# main_IO.net
KiCad netlist of a schematic drawn in Altium Designer
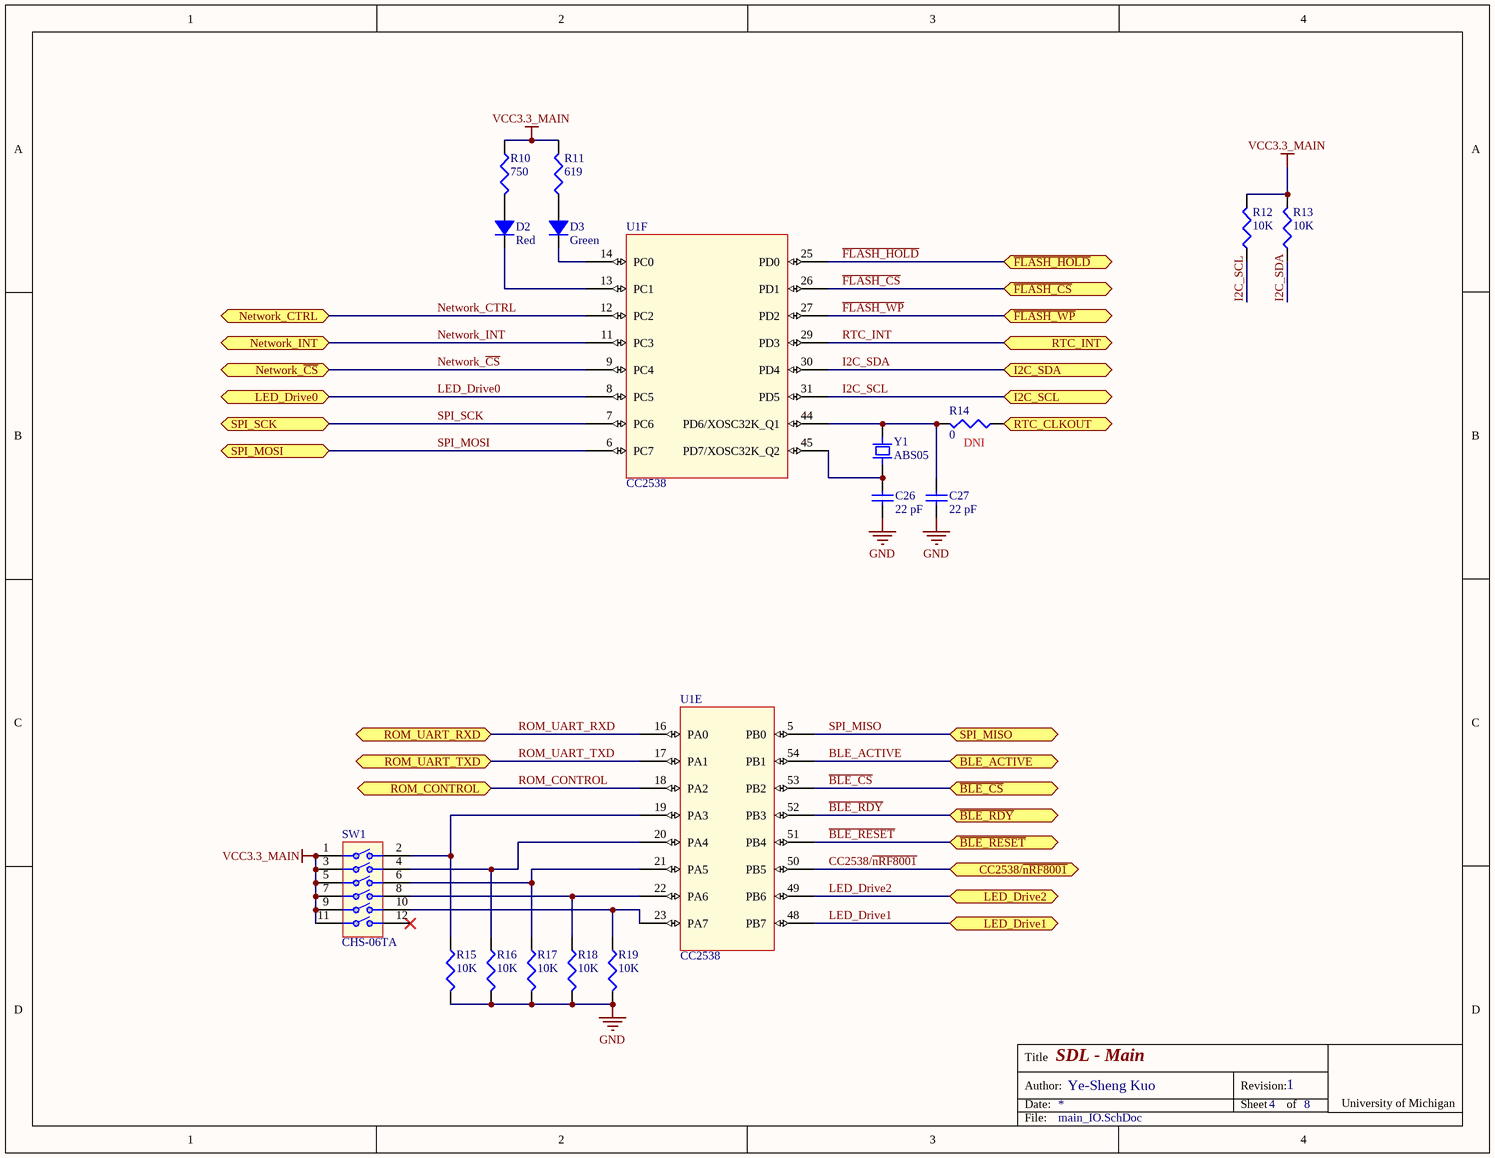
[diagram p0: main_IO.SchDoc]

(export (version "E")
  (design (tool "Eeschema 10.0.6"))
  (components
    (comp (ref "C26")
      (value "22 pF")
      (footprint "0402")
      (description "Ceramic capacitor, 22 pF, 0402 package")
      (fields (field (name "TOLERANCE") "2%") (field (name "Comment") "Ceramic capacitor"))
      (libsource (lib "rlc") (part "C_22p_0402_ceramic"))
    )
    (comp (ref "C27")
      (value "22 pF")
      (footprint "0402")
      (description "Ceramic capacitor, 22 pF, 0402 package")
      (fields (field (name "TOLERANCE") "2%") (field (name "Comment") "Ceramic capacitor"))
      (libsource (lib "rlc") (part "C_22p_0402_ceramic"))
    )
    (comp (ref "D2")
      (value "LED, Red")
      (footprint "0402 - DIODE")
      (description "LED, Red, 0402")
      (fields (field (name "COLOR") "Red"))
      (libsource (lib "rlc") (part "D_LED_RED_0402"))
    )
    (comp (ref "D3")
      (value "LED, Green")
      (footprint "0402 - DIODE")
      (description "LED, Green,  0402")
      (fields (field (name "COLOR") "Green"))
      (libsource (lib "rlc") (part "D_LED_GREEN_0402"))
    )
    (comp (ref "R10")
      (value "750")
      (footprint "0402")
      (description "Chip resistor, 750, 0402 package")
      (fields (field (name "TOLERANCE") "1%") (field (name "POWER") "1/16 W"))
      (libsource (lib "rlc") (part "R_750_0402"))
    )
    (comp (ref "R11")
      (value "619")
      (footprint "0402")
      (description "Chip resistor, 619, 0402 package")
      (fields (field (name "TOLERANCE") "1%") (field (name "POWER") "1/16 W"))
      (libsource (lib "rlc") (part "R_619_0402"))
    )
    (comp (ref "R12")
      (value "10K")
      (footprint "0402")
      (description "Chip resistor, 10K, 0402 package")
      (fields (field (name "TOLERANCE") "1%") (field (name "POWER") "1/16 W"))
      (libsource (lib "rlc") (part "R_10K_0402"))
    )
    (comp (ref "R13")
      (value "10K")
      (footprint "0402")
      (description "Chip resistor, 10K, 0402 package")
      (fields (field (name "TOLERANCE") "1%") (field (name "POWER") "1/16 W"))
      (libsource (lib "rlc") (part "R_10K_0402"))
    )
    (comp (ref "R14")
      (value "0")
      (footprint "0402")
      (description "Chip resistor, 0, 0402 package")
      (fields (field (name "Comment") "Chip resistor"))
      (libsource (lib "rlc") (part "R_0_0402"))
    )
    (comp (ref "R15")
      (value "10K")
      (footprint "0402")
      (description "Chip resistor, 10K, 0402 package")
      (fields (field (name "TOLERANCE") "1%") (field (name "POWER") "1/16 W"))
      (libsource (lib "rlc") (part "R_10K_0402"))
    )
    (comp (ref "R16")
      (value "10K")
      (footprint "0402")
      (description "Chip resistor, 10K, 0402 package")
      (fields (field (name "TOLERANCE") "1%") (field (name "POWER") "1/16 W"))
      (libsource (lib "rlc") (part "R_10K_0402"))
    )
    (comp (ref "R17")
      (value "10K")
      (footprint "0402")
      (description "Chip resistor, 10K, 0402 package")
      (fields (field (name "TOLERANCE") "1%") (field (name "POWER") "1/16 W"))
      (libsource (lib "rlc") (part "R_10K_0402"))
    )
    (comp (ref "R18")
      (value "10K")
      (footprint "0402")
      (description "Chip resistor, 10K, 0402 package")
      (fields (field (name "TOLERANCE") "1%") (field (name "POWER") "1/16 W"))
      (libsource (lib "rlc") (part "R_10K_0402"))
    )
    (comp (ref "R19")
      (value "10K")
      (footprint "0402")
      (description "Chip resistor, 10K, 0402 package")
      (fields (field (name "TOLERANCE") "1%") (field (name "POWER") "1/16 W"))
      (libsource (lib "rlc") (part "R_10K_0402"))
    )
    (comp (ref "SW1")
      (value "CHS-06TA")
      (footprint "CHS-06TA")
      (description "SLIDE SWITCHES")
      (libsource (lib "sdl") (part "CHS-06TA"))
    )
    (comp (ref "U1")
      (value "CC2538")
      (footprint "QFN56")
      (description "A Powerful System-On-Chip for 2.4-GHz IEEE 802.15.4, 6LoWPAN  and ZigBee Applications")
      (libsource (lib "sdl") (part "CC2538"))
    )
    (comp (ref "Y1")
      (value "ABS05")
      (footprint "ABS05")
      (description "32768 Hz SMD Low profile crystal")
      (libsource (lib "crystal_oscillators_rtc") (part "ABS05"))
    )
  )
  (nets
    (net (code "1") (name "/BLE_ACTIVE") (class "Default")
      (node (ref "U1") (pin "54") (pinfunction "PB1_54") (pintype "bidirectional"))
    )
    (net (code "2") (name "/CC2538{slash}~{nRF8001}") (class "Default")
      (node (ref "U1") (pin "50") (pinfunction "PB5_50") (pintype "bidirectional"))
    )
    (net (code "3") (name "/I2C_SCL") (class "Default")
      (node (ref "R12") (pin "2") (pintype "passive"))
      (node (ref "U1") (pin "31") (pinfunction "PD5_31") (pintype "bidirectional"))
    )
    (net (code "4") (name "/I2C_SDA") (class "Default")
      (node (ref "R13") (pin "2") (pintype "passive"))
      (node (ref "U1") (pin "30") (pinfunction "PD4_30") (pintype "bidirectional"))
    )
    (net (code "5") (name "/LED_Drive0") (class "Default")
      (node (ref "U1") (pin "8") (pinfunction "PC5_8") (pintype "bidirectional"))
    )
    (net (code "6") (name "/LED_Drive1") (class "Default")
      (node (ref "U1") (pin "48") (pinfunction "PB7_48") (pintype "bidirectional"))
    )
    (net (code "7") (name "/LED_Drive2") (class "Default")
      (node (ref "U1") (pin "49") (pinfunction "PB6_49") (pintype "bidirectional"))
    )
    (net (code "8") (name "/Network_CTRL") (class "Default")
      (node (ref "U1") (pin "12") (pinfunction "PC2_12") (pintype "bidirectional"))
    )
    (net (code "9") (name "/Network_INT") (class "Default")
      (node (ref "U1") (pin "11") (pinfunction "PC3_11") (pintype "bidirectional"))
    )
    (net (code "10") (name "/Network_~{CS}") (class "Default")
      (node (ref "U1") (pin "9") (pinfunction "PC4_9") (pintype "bidirectional"))
    )
    (net (code "11") (name "/ROM_CONTROL") (class "Default")
      (node (ref "U1") (pin "18") (pinfunction "PA2_18") (pintype "bidirectional"))
    )
    (net (code "12") (name "/ROM_UART_RXD") (class "Default")
      (node (ref "U1") (pin "16") (pinfunction "PA0_16") (pintype "bidirectional"))
    )
    (net (code "13") (name "/ROM_UART_TXD") (class "Default")
      (node (ref "U1") (pin "17") (pinfunction "PA1_17") (pintype "bidirectional"))
    )
    (net (code "14") (name "/RTC_CLKOUT") (class "Default") (node (ref "R14") (pin "2") (pintype "passive")))
    (net (code "15") (name "/RTC_INT") (class "Default")
      (node (ref "U1") (pin "29") (pinfunction "PD3_29") (pintype "bidirectional"))
    )
    (net (code "16") (name "/SPI_MISO") (class "Default")
      (node (ref "U1") (pin "5") (pinfunction "PB0_5") (pintype "bidirectional"))
    )
    (net (code "17") (name "/SPI_MOSI") (class "Default")
      (node (ref "U1") (pin "6") (pinfunction "PC7_6") (pintype "bidirectional"))
    )
    (net (code "18") (name "/SPI_SCK") (class "Default")
      (node (ref "U1") (pin "7") (pinfunction "PC6_7") (pintype "bidirectional"))
    )
    (net (code "19") (name "/~{BLE_CS}") (class "Default")
      (node (ref "U1") (pin "53") (pinfunction "PB2_53") (pintype "bidirectional"))
    )
    (net (code "20") (name "/~{BLE_RDY}") (class "Default")
      (node (ref "U1") (pin "52") (pinfunction "PB3_52") (pintype "bidirectional"))
    )
    (net (code "21") (name "/~{BLE_RESET}") (class "Default")
      (node (ref "U1") (pin "51") (pinfunction "PB4_51") (pintype "bidirectional"))
    )
    (net (code "22") (name "/~{FLASH_CS}") (class "Default")
      (node (ref "U1") (pin "26") (pinfunction "PD1_26") (pintype "bidirectional"))
    )
    (net (code "23") (name "/~{FLASH_HOLD}") (class "Default")
      (node (ref "U1") (pin "25") (pinfunction "PD0_25") (pintype "bidirectional"))
    )
    (net (code "24") (name "/~{FLASH_WP}") (class "Default")
      (node (ref "U1") (pin "27") (pinfunction "PD2_27") (pintype "bidirectional"))
    )
    (net (code "25") (name "GND") (class "Default")
      (node (ref "C26") (pin "2") (pintype "passive"))
      (node (ref "C27") (pin "2") (pintype "passive"))
      (node (ref "R15") (pin "1") (pintype "passive"))
      (node (ref "R16") (pin "1") (pintype "passive"))
      (node (ref "R17") (pin "1") (pintype "passive"))
      (node (ref "R18") (pin "1") (pintype "passive"))
      (node (ref "R19") (pin "1") (pintype "passive"))
    )
    (net (code "26") (name "Net-(D2-Pad1)") (class "Default")
      (node (ref "D2") (pin "1") (pintype "passive"))
      (node (ref "R10") (pin "1") (pintype "passive"))
    )
    (net (code "27") (name "Net-(D3-Pad1)") (class "Default")
      (node (ref "D3") (pin "1") (pintype "passive"))
      (node (ref "R11") (pin "2") (pintype "passive"))
    )
    (net (code "28") (name "Net-(U1E-PA3)") (class "Default")
      (node (ref "R15") (pin "2") (pintype "passive"))
      (node (ref "SW1") (pin "2") (pinfunction "2_2") (pintype "passive"))
      (node (ref "U1") (pin "19") (pinfunction "PA3_19") (pintype "bidirectional"))
    )
    (net (code "29") (name "Net-(U1E-PA4)") (class "Default")
      (node (ref "R16") (pin "2") (pintype "passive"))
      (node (ref "SW1") (pin "4") (pinfunction "4_4") (pintype "passive"))
      (node (ref "U1") (pin "20") (pinfunction "PA4_20") (pintype "bidirectional"))
    )
    (net (code "30") (name "Net-(U1E-PA5)") (class "Default")
      (node (ref "R17") (pin "2") (pintype "passive"))
      (node (ref "SW1") (pin "6") (pinfunction "6_6") (pintype "passive"))
      (node (ref "U1") (pin "21") (pinfunction "PA5_21") (pintype "bidirectional"))
    )
    (net (code "31") (name "Net-(U1E-PA6)") (class "Default")
      (node (ref "R18") (pin "2") (pintype "passive"))
      (node (ref "SW1") (pin "8") (pinfunction "8_8") (pintype "passive"))
      (node (ref "U1") (pin "22") (pinfunction "PA6_22") (pintype "bidirectional"))
    )
    (net (code "32") (name "Net-(U1E-PA7)") (class "Default")
      (node (ref "R19") (pin "2") (pintype "passive"))
      (node (ref "SW1") (pin "10") (pinfunction "10_10") (pintype "passive"))
      (node (ref "U1") (pin "23") (pinfunction "PA7_23") (pintype "bidirectional"))
    )
    (net (code "33") (name "Net-(U1F-PC0)") (class "Default")
      (node (ref "D3") (pin "2") (pintype "passive"))
      (node (ref "U1") (pin "14") (pinfunction "PC0_14") (pintype "bidirectional"))
    )
    (net (code "34") (name "Net-(U1F-PC1)") (class "Default")
      (node (ref "D2") (pin "2") (pintype "passive"))
      (node (ref "U1") (pin "13") (pinfunction "PC1_13") (pintype "bidirectional"))
    )
    (net (code "35") (name "Net-(U1F-PD6{slash}XOSC32K_Q1)") (class "Default")
      (node (ref "C27") (pin "1") (pintype "passive"))
      (node (ref "R14") (pin "1") (pintype "passive"))
      (node (ref "U1") (pin "44") (pinfunction "PD6/XOSC32K_Q1_44") (pintype "bidirectional"))
      (node (ref "Y1") (pin "1") (pintype "passive"))
    )
    (net (code "36") (name "Net-(U1F-PD7{slash}XOSC32K_Q2)") (class "Default")
      (node (ref "C26") (pin "1") (pintype "passive"))
      (node (ref "U1") (pin "45") (pinfunction "PD7/XOSC32K_Q2_45") (pintype "bidirectional"))
      (node (ref "Y1") (pin "2") (pintype "passive"))
    )
    (net (code "37") (name "VCC3.3_MAIN") (class "Default")
      (node (ref "R10") (pin "2") (pintype "passive"))
      (node (ref "R11") (pin "1") (pintype "passive"))
      (node (ref "R12") (pin "1") (pintype "passive"))
      (node (ref "R13") (pin "1") (pintype "passive"))
      (node (ref "SW1") (pin "1") (pinfunction "1_1") (pintype "passive"))
      (node (ref "SW1") (pin "11") (pinfunction "11_11") (pintype "passive"))
      (node (ref "SW1") (pin "3") (pinfunction "3_3") (pintype "passive"))
      (node (ref "SW1") (pin "5") (pinfunction "5_5") (pintype "passive"))
      (node (ref "SW1") (pin "7") (pinfunction "7_7") (pintype "passive"))
      (node (ref "SW1") (pin "9") (pinfunction "9_9") (pintype "passive"))
    )
    (net (code "38") (name "unconnected-(SW1-Pad12)") (class "Default")
      (node (ref "SW1") (pin "12") (pinfunction "12_12") (pintype "passive+no_connect"))
    )
  )
)
